# picopsh.net
KiCad netlist of a schematic drawn in EAGLE
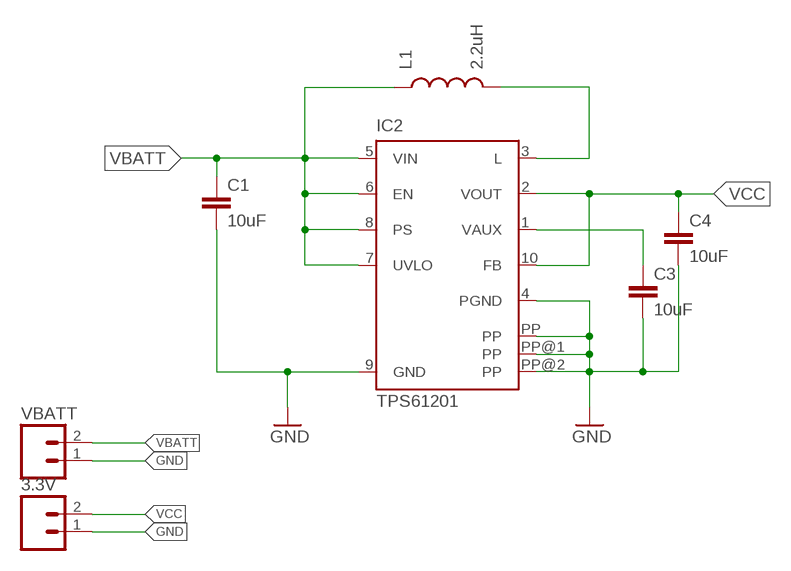
[diagram p0: schematic, sheet 1]

(export (version "E")
  (design (tool "Eeschema 10.0.6"))
  (components
    (comp (ref "3.3V")
      (value "M02PTH")
      (footprint "eagle-import:1X02")
      (libsource (lib "eagle-import") (part "M02PTH"))
    )
    (comp (ref "C1")
      (value "10uF")
      (footprint "eagle-import:1206")
      (libsource (lib "eagle-import") (part "CAP1206"))
    )
    (comp (ref "C3")
      (value "10uF")
      (footprint "eagle-import:1206")
      (libsource (lib "eagle-import") (part "CAP1206"))
    )
    (comp (ref "C4")
      (value "10uF")
      (footprint "eagle-import:1206")
      (libsource (lib "eagle-import") (part "CAP1206"))
    )
    (comp (ref "IC2")
      (value "TPS61201")
      (footprint "eagle-import:S-PDSO-N10")
      (fields (field (name "MPN") "TPS61201DRCT"))
      (libsource (lib "eagle-import") (part "TPS61201"))
    )
    (comp (ref "L1")
      (value "2.2uH")
      (footprint "eagle-import:ELLVGG_INDUCTOR")
      (libsource (lib "eagle-import") (part "ELLVGG_INDUCTOR"))
    )
    (comp (ref "VBATT")
      (value "M02PTH")
      (footprint "eagle-import:1X02")
      (libsource (lib "eagle-import") (part "M02PTH"))
    )
  )
  (nets
    (net (code "1") (name "GND") (class "Default")
      (node (ref "3.3V") (pin "1") (pinfunction "1_1") (pintype "passive"))
      (node (ref "C1") (pin "2") (pinfunction "2_2") (pintype "passive"))
      (node (ref "C3") (pin "2") (pinfunction "2_2") (pintype "passive"))
      (node (ref "C4") (pin "2") (pinfunction "2_2") (pintype "passive"))
      (node (ref "IC2") (pin "4") (pinfunction "PGND_4") (pintype "power_in"))
      (node (ref "IC2") (pin "9") (pinfunction "GND_9") (pintype "power_in"))
      (node (ref "IC2") (pin "PP") (pinfunction "PP_PP") (pintype "power_in"))
      (node (ref "IC2") (pin "PP@1") (pinfunction "PP_PP@1") (pintype "power_in"))
      (node (ref "IC2") (pin "PP@2") (pinfunction "PP_PP@2") (pintype "power_in"))
      (node (ref "VBATT") (pin "1") (pinfunction "1_1") (pintype "passive"))
    )
    (net (code "2") (name "Net-(IC2-L)") (class "Default")
      (node (ref "IC2") (pin "3") (pinfunction "L_3") (pintype "input"))
      (node (ref "L1") (pin "P$2") (pinfunction "2_P$2") (pintype "passive"))
    )
    (net (code "3") (name "Net-(IC2-VAUX)") (class "Default")
      (node (ref "C3") (pin "1") (pinfunction "1_1") (pintype "passive"))
      (node (ref "IC2") (pin "1") (pinfunction "VAUX_1") (pintype "bidirectional"))
    )
    (net (code "4") (name "VBATT") (class "Default")
      (node (ref "C1") (pin "1") (pinfunction "1_1") (pintype "passive"))
      (node (ref "IC2") (pin "5") (pinfunction "VIN_5") (pintype "input"))
      (node (ref "IC2") (pin "6") (pinfunction "EN_6") (pintype "input"))
      (node (ref "IC2") (pin "7") (pinfunction "UVLO_7") (pintype "input"))
      (node (ref "IC2") (pin "8") (pinfunction "PS_8") (pintype "input"))
      (node (ref "L1") (pin "P$1") (pinfunction "1_P$1") (pintype "passive"))
      (node (ref "VBATT") (pin "2") (pinfunction "2_2") (pintype "passive"))
    )
    (net (code "5") (name "VCC") (class "Default")
      (node (ref "3.3V") (pin "2") (pinfunction "2_2") (pintype "passive"))
      (node (ref "C4") (pin "1") (pinfunction "1_1") (pintype "passive"))
      (node (ref "IC2") (pin "10") (pinfunction "FB_10") (pintype "input"))
      (node (ref "IC2") (pin "2") (pinfunction "VOUT_2") (pintype "passive"))
    )
  )
)
